# probe_v2_1.net
KiCad netlist of a schematic drawn in EAGLE
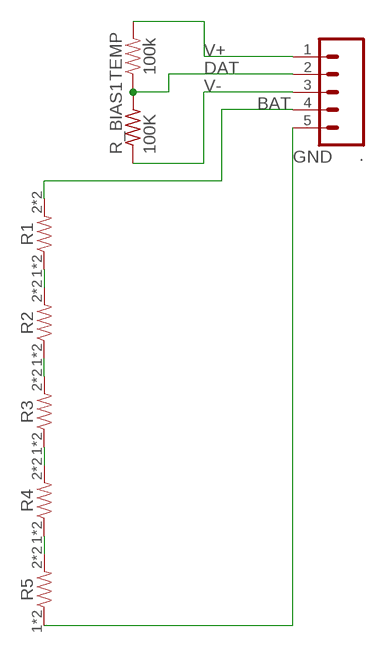
[diagram p0: schematic, sheet 1]

(export (version "E")
  (design (tool "Eeschema 10.0.6"))
  (components
    (comp (ref ".")
      (value "CONN_05NO_SILK")
      (footprint "eagle-import:1X05_NO_SILK")
      (libsource (lib "eagle-import") (part "CONN_05NO_SILK"))
    )
    (comp (ref "R1")
      (value "DRES")
      (footprint "eagle-import:0603")
      (libsource (lib "eagle-import") (part "DRES"))
    )
    (comp (ref "R2")
      (value "DRES")
      (footprint "eagle-import:0603")
      (libsource (lib "eagle-import") (part "DRES"))
    )
    (comp (ref "R3")
      (value "DRES")
      (footprint "eagle-import:0603")
      (libsource (lib "eagle-import") (part "DRES"))
    )
    (comp (ref "R4")
      (value "DRES")
      (footprint "eagle-import:0603")
      (libsource (lib "eagle-import") (part "DRES"))
    )
    (comp (ref "R5")
      (value "DRES")
      (footprint "eagle-import:0603")
      (libsource (lib "eagle-import") (part "DRES"))
    )
    (comp (ref "R_BIAS1")
      (value "100K")
      (footprint "eagle-import:0805-THM")
      (libsource (lib "eagle-import") (part "FLIPFLOP-RES"))
    )
    (comp (ref "TEMP")
      (value "100k")
      (footprint "eagle-import:0603")
      (libsource (lib "eagle-import") (part "1.8MOHM"))
    )
  )
  (nets
    (net (code "1") (name "/BAT") (class "Default")
      (node (ref ".") (pin "4") (pinfunction "4_4") (pintype "passive"))
      (node (ref "R1") (pin "2") (pinfunction "2_2") (pintype "passive"))
      (node (ref "R1") (pin "P$2") (pinfunction "2_P$2") (pintype "passive"))
    )
    (net (code "2") (name "/DAT") (class "Default")
      (node (ref ".") (pin "2") (pinfunction "2_2") (pintype "passive"))
      (node (ref "R_BIAS1") (pin "2") (pinfunction "2_2") (pintype "passive"))
      (node (ref "TEMP") (pin "1") (pinfunction "1_1") (pintype "passive"))
    )
    (net (code "3") (name "/GND") (class "Default")
      (node (ref ".") (pin "5") (pinfunction "5_5") (pintype "passive"))
      (node (ref "R5") (pin "1") (pinfunction "1_1") (pintype "passive"))
      (node (ref "R5") (pin "P$1") (pinfunction "1_P$1") (pintype "passive"))
    )
    (net (code "4") (name "/V+") (class "Default")
      (node (ref ".") (pin "1") (pinfunction "1_1") (pintype "passive"))
      (node (ref "TEMP") (pin "2") (pinfunction "2_2") (pintype "passive"))
    )
    (net (code "5") (name "/V-") (class "Default")
      (node (ref ".") (pin "3") (pinfunction "3_3") (pintype "passive"))
      (node (ref "R_BIAS1") (pin "1") (pinfunction "1_1") (pintype "passive"))
    )
    (net (code "6") (name "Net-(R1-1-PadP$1)") (class "Default")
      (node (ref "R1") (pin "1") (pinfunction "1_1") (pintype "passive"))
      (node (ref "R1") (pin "P$1") (pinfunction "1_P$1") (pintype "passive"))
      (node (ref "R2") (pin "2") (pinfunction "2_2") (pintype "passive"))
      (node (ref "R2") (pin "P$2") (pinfunction "2_P$2") (pintype "passive"))
    )
    (net (code "7") (name "Net-(R2-1-PadP$1)") (class "Default")
      (node (ref "R2") (pin "1") (pinfunction "1_1") (pintype "passive"))
      (node (ref "R2") (pin "P$1") (pinfunction "1_P$1") (pintype "passive"))
      (node (ref "R3") (pin "2") (pinfunction "2_2") (pintype "passive"))
      (node (ref "R3") (pin "P$2") (pinfunction "2_P$2") (pintype "passive"))
    )
    (net (code "8") (name "Net-(R3-1-PadP$1)") (class "Default")
      (node (ref "R3") (pin "1") (pinfunction "1_1") (pintype "passive"))
      (node (ref "R3") (pin "P$1") (pinfunction "1_P$1") (pintype "passive"))
      (node (ref "R4") (pin "2") (pinfunction "2_2") (pintype "passive"))
      (node (ref "R4") (pin "P$2") (pinfunction "2_P$2") (pintype "passive"))
    )
    (net (code "9") (name "Net-(R4-1-PadP$1)") (class "Default")
      (node (ref "R4") (pin "1") (pinfunction "1_1") (pintype "passive"))
      (node (ref "R4") (pin "P$1") (pinfunction "1_P$1") (pintype "passive"))
      (node (ref "R5") (pin "2") (pinfunction "2_2") (pintype "passive"))
      (node (ref "R5") (pin "P$2") (pinfunction "2_P$2") (pintype "passive"))
    )
  )
)
